# 10_RSSI1.net
KiCad netlist of a schematic drawn in Altium Designer
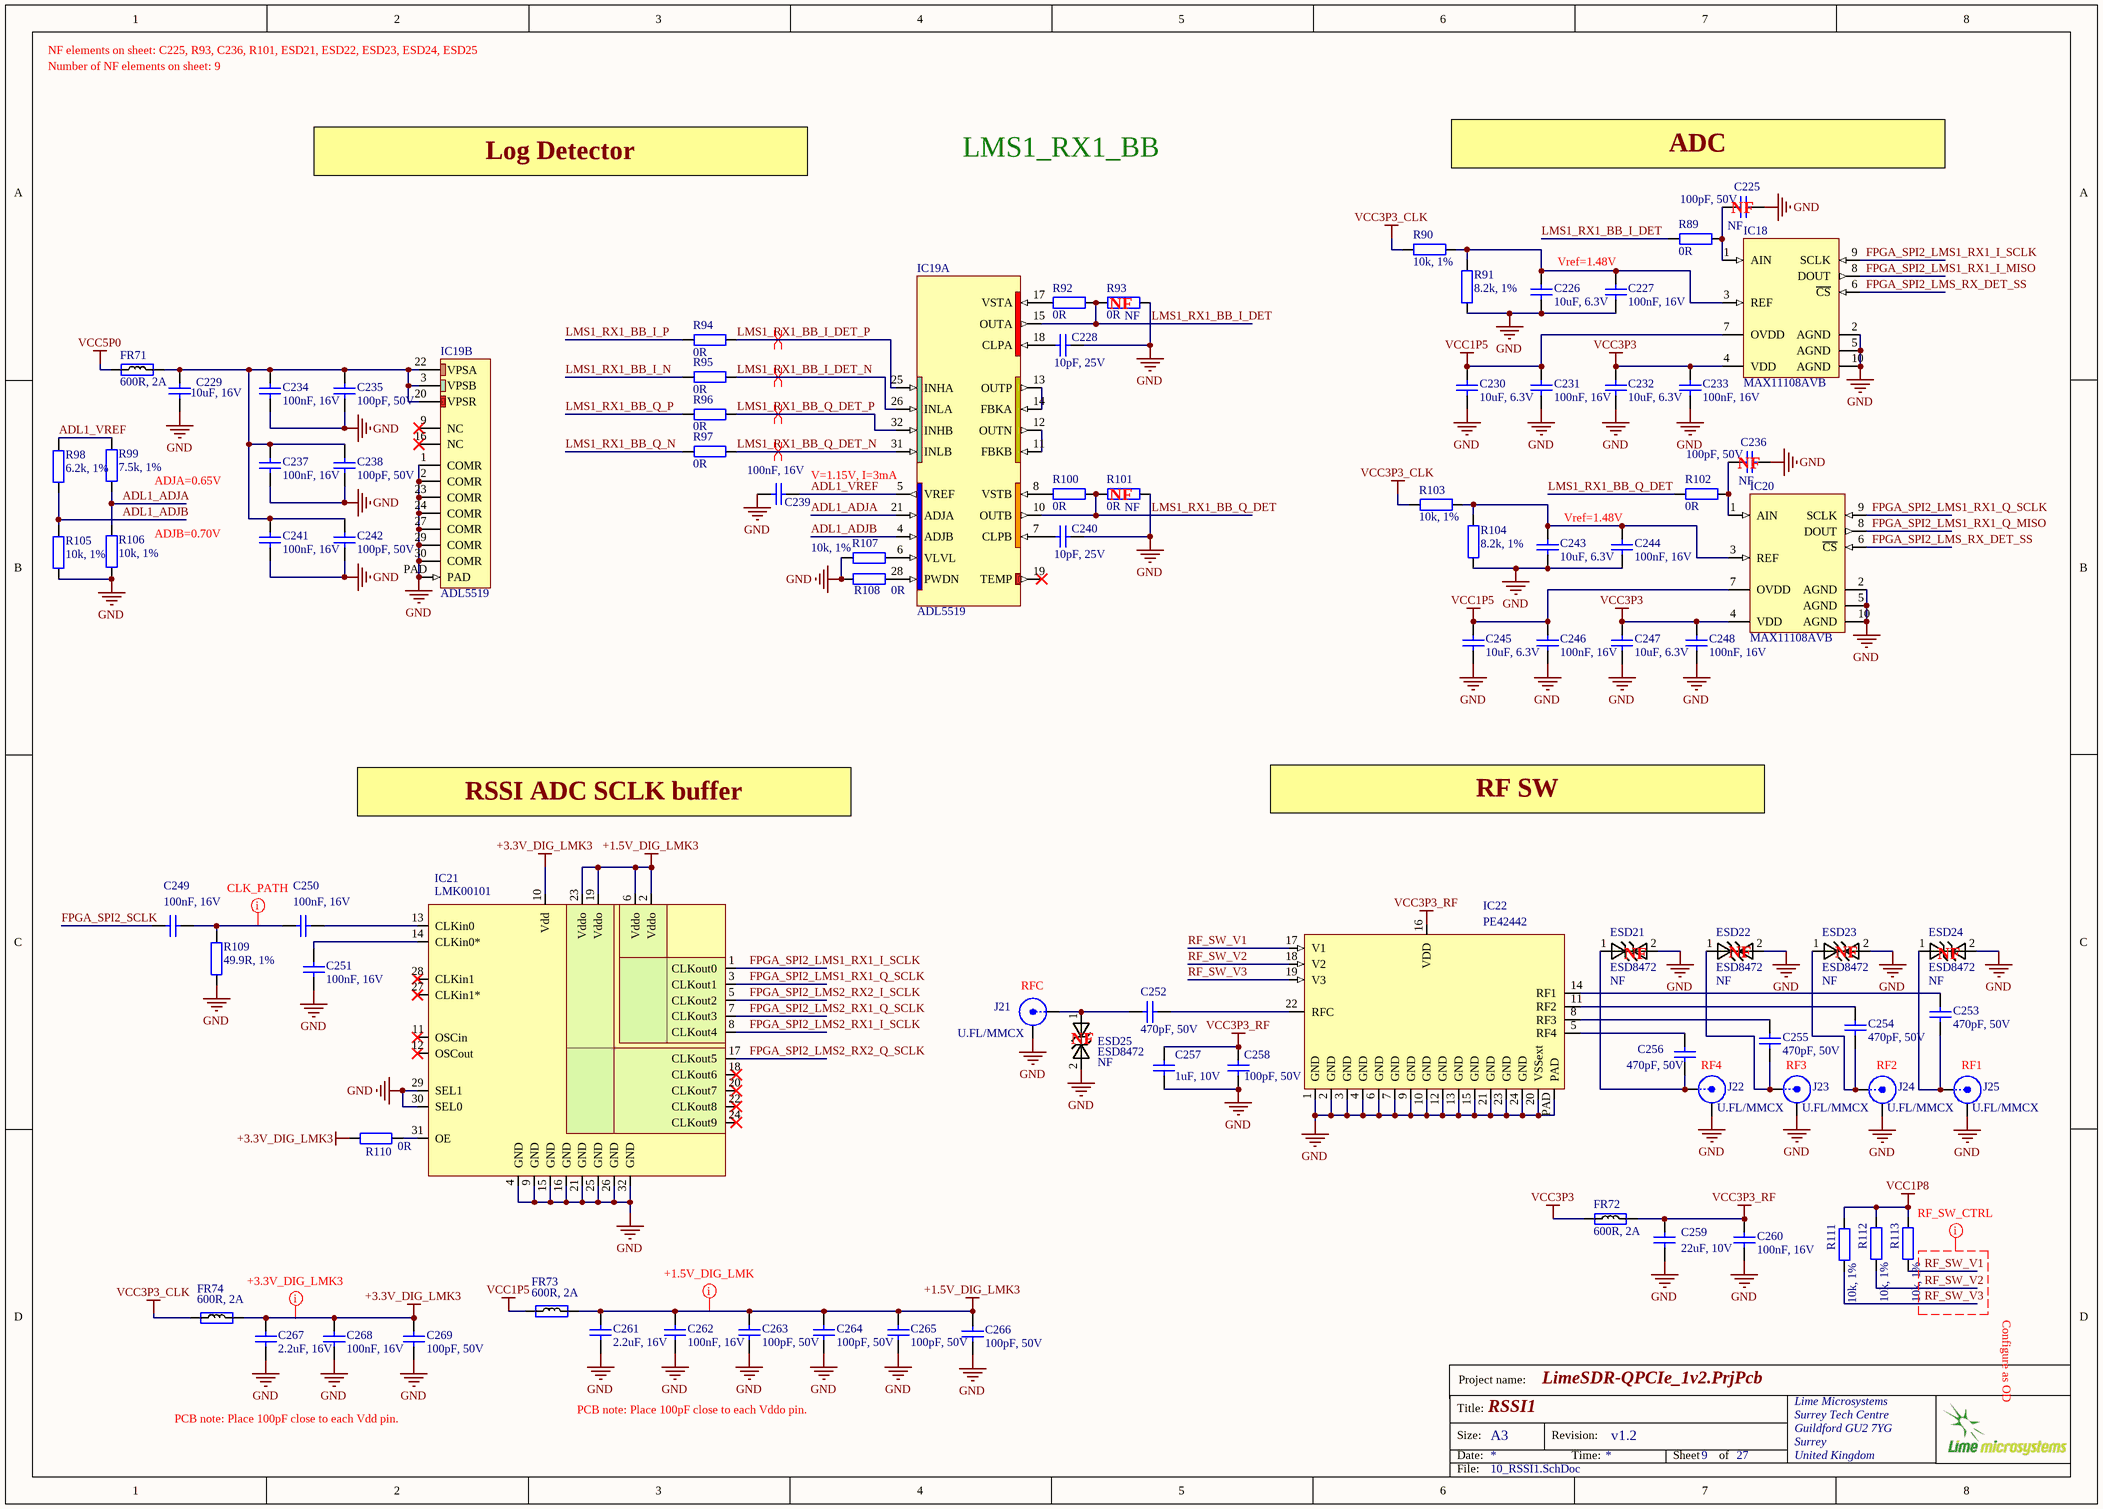
[diagram p0: 10_RSSI1.SchDoc]

(export (version "E")
  (design (tool "Eeschema 10.0.6"))
  (components
    (comp (ref "C225")
      (value "100pF, 50V")
      (footprint "CAP0402")
      (fields
        (field (name "ASSEMBLY INFO") "NF")
        (field (name "MANUFACTURER") "Yageo")
        (field (name "TOLERANCE") "±5%")
      )
      (libsource (lib "LimeMicroAltiumLib_schLib") (part "Cap_0402"))
    )
    (comp (ref "C226")
      (value "10uF, 6.3V")
      (footprint "CAP0603")
      (fields (field (name "TOLERANCE") "±20%") (field (name "MANUFACTURER") "Yageo"))
      (libsource (lib "LimeFPGAboard_schLib") (part "Cap_0603"))
    )
    (comp (ref "C227")
      (value "100nF, 16V")
      (footprint "CAP0402")
      (fields
        (field (name "MANUFACTURER") "Murata Electronics")
        (field (name "TOLERANCE") "10 %")
        (field (name "MANUFACTURER PART NUMBER") "GRM155R71C104KA88D")
      )
      (libsource (lib "LimeMicroAltiumLib_schLib") (part "Cap_0402"))
    )
    (comp (ref "C228")
      (value "10pF, 25V")
      (footprint "CAP0402")
      (fields (field (name "MANUFACTURER") "AVX"))
      (libsource (lib "LimeMicroAltiumLib_schLib") (part "Cap_0402"))
    )
    (comp (ref "C229")
      (value "10uF, 16V")
      (footprint "CAP0603")
      (fields (field (name "MANUFACTURER") "Yageo") (field (name "TOLERANCE") "±20%"))
      (libsource (lib "LimeMicroAltiumLib_schLib") (part "Cap_0603"))
    )
    (comp (ref "C230")
      (value "10uF, 6.3V")
      (footprint "CAP0603")
      (fields (field (name "TOLERANCE") "±20%") (field (name "MANUFACTURER") "Yageo"))
      (libsource (lib "LimeFPGAboard_schLib") (part "Cap_0603"))
    )
    (comp (ref "C231")
      (value "100nF, 16V")
      (footprint "CAP0402")
      (fields
        (field (name "MANUFACTURER") "Murata Electronics")
        (field (name "TOLERANCE") "10 %")
        (field (name "MANUFACTURER PART NUMBER") "GRM155R71C104KA88D")
      )
      (libsource (lib "LimeMicroAltiumLib_schLib") (part "Cap_0402"))
    )
    (comp (ref "C232")
      (value "10uF, 6.3V")
      (footprint "CAP0603")
      (fields (field (name "TOLERANCE") "±20%") (field (name "MANUFACTURER") "Yageo"))
      (libsource (lib "LimeFPGAboard_schLib") (part "Cap_0603"))
    )
    (comp (ref "C233")
      (value "100nF, 16V")
      (footprint "CAP0402")
      (fields
        (field (name "MANUFACTURER") "Murata Electronics")
        (field (name "TOLERANCE") "10 %")
        (field (name "MANUFACTURER PART NUMBER") "GRM155R71C104KA88D")
      )
      (libsource (lib "LimeMicroAltiumLib_schLib") (part "Cap_0402"))
    )
    (comp (ref "C234")
      (value "100nF, 16V")
      (footprint "CAP0402")
      (fields
        (field (name "MANUFACTURER") "Murata Electronics")
        (field (name "TOLERANCE") "10 %")
        (field (name "MANUFACTURER PART NUMBER") "GRM155R71C104KA88D")
      )
      (libsource (lib "LimeMicroAltiumLib_schLib") (part "Cap_0402"))
    )
    (comp (ref "C235")
      (value "100pF, 50V")
      (footprint "CAP0402")
      (fields (field (name "MANUFACTURER") "Yageo") (field (name "TOLERANCE") "±5%"))
      (libsource (lib "LimeMicroAltiumLib_schLib") (part "Cap_0402"))
    )
    (comp (ref "C236")
      (value "100pF, 50V")
      (footprint "CAP0402")
      (fields
        (field (name "ASSEMBLY INFO") "NF")
        (field (name "MANUFACTURER") "Yageo")
        (field (name "TOLERANCE") "±5%")
      )
      (libsource (lib "LimeMicroAltiumLib_schLib") (part "Cap_0402"))
    )
    (comp (ref "C237")
      (value "100nF, 16V")
      (footprint "CAP0402")
      (fields
        (field (name "MANUFACTURER") "Murata Electronics")
        (field (name "TOLERANCE") "10 %")
        (field (name "MANUFACTURER PART NUMBER") "GRM155R71C104KA88D")
      )
      (libsource (lib "LimeMicroAltiumLib_schLib") (part "Cap_0402"))
    )
    (comp (ref "C238")
      (value "100pF, 50V")
      (footprint "CAP0402")
      (fields (field (name "MANUFACTURER") "Yageo") (field (name "TOLERANCE") "±5%"))
      (libsource (lib "LimeMicroAltiumLib_schLib") (part "Cap_0402"))
    )
    (comp (ref "C239")
      (value "100nF, 16V")
      (footprint "CAP0402")
      (fields
        (field (name "MANUFACTURER") "Murata Electronics")
        (field (name "TOLERANCE") "10 %")
        (field (name "MANUFACTURER PART NUMBER") "GRM155R71C104KA88D")
      )
      (libsource (lib "LimeMicroAltiumLib_schLib") (part "Cap_0402"))
    )
    (comp (ref "C240")
      (value "10pF, 25V")
      (footprint "CAP0402")
      (fields (field (name "MANUFACTURER") "AVX"))
      (libsource (lib "LimeMicroAltiumLib_schLib") (part "Cap_0402"))
    )
    (comp (ref "C241")
      (value "100nF, 16V")
      (footprint "CAP0402")
      (fields
        (field (name "MANUFACTURER") "Murata Electronics")
        (field (name "TOLERANCE") "10 %")
        (field (name "MANUFACTURER PART NUMBER") "GRM155R71C104KA88D")
      )
      (libsource (lib "LimeMicroAltiumLib_schLib") (part "Cap_0402"))
    )
    (comp (ref "C242")
      (value "100pF, 50V")
      (footprint "CAP0402")
      (fields (field (name "MANUFACTURER") "Yageo") (field (name "TOLERANCE") "±5%"))
      (libsource (lib "LimeMicroAltiumLib_schLib") (part "Cap_0402"))
    )
    (comp (ref "C243")
      (value "10uF, 6.3V")
      (footprint "CAP0603")
      (fields (field (name "TOLERANCE") "±20%") (field (name "MANUFACTURER") "Yageo"))
      (libsource (lib "LimeFPGAboard_schLib") (part "Cap_0603"))
    )
    (comp (ref "C244")
      (value "100nF, 16V")
      (footprint "CAP0402")
      (fields
        (field (name "MANUFACTURER") "Murata Electronics")
        (field (name "TOLERANCE") "10 %")
        (field (name "MANUFACTURER PART NUMBER") "GRM155R71C104KA88D")
      )
      (libsource (lib "LimeMicroAltiumLib_schLib") (part "Cap_0402"))
    )
    (comp (ref "C245")
      (value "10uF, 6.3V")
      (footprint "CAP0603")
      (fields (field (name "TOLERANCE") "±20%") (field (name "MANUFACTURER") "Yageo"))
      (libsource (lib "LimeFPGAboard_schLib") (part "Cap_0603"))
    )
    (comp (ref "C246")
      (value "100nF, 16V")
      (footprint "CAP0402")
      (fields
        (field (name "MANUFACTURER") "Murata Electronics")
        (field (name "TOLERANCE") "10 %")
        (field (name "MANUFACTURER PART NUMBER") "GRM155R71C104KA88D")
      )
      (libsource (lib "LimeMicroAltiumLib_schLib") (part "Cap_0402"))
    )
    (comp (ref "C247")
      (value "10uF, 6.3V")
      (footprint "CAP0603")
      (fields (field (name "TOLERANCE") "±20%") (field (name "MANUFACTURER") "Yageo"))
      (libsource (lib "LimeFPGAboard_schLib") (part "Cap_0603"))
    )
    (comp (ref "C248")
      (value "100nF, 16V")
      (footprint "CAP0402")
      (fields
        (field (name "MANUFACTURER") "Murata Electronics")
        (field (name "TOLERANCE") "10 %")
        (field (name "MANUFACTURER PART NUMBER") "GRM155R71C104KA88D")
      )
      (libsource (lib "LimeMicroAltiumLib_schLib") (part "Cap_0402"))
    )
    (comp (ref "C249")
      (value "100nF, 16V")
      (footprint "CAP0402")
      (fields
        (field (name "MANUFACTURER") "Murata Electronics")
        (field (name "TOLERANCE") "10 %")
        (field (name "MANUFACTURER PART NUMBER") "GRM155R71C104KA88D")
      )
      (libsource (lib "LimeMicroAltiumLib_schLib") (part "Cap_0402"))
    )
    (comp (ref "C250")
      (value "100nF, 16V")
      (footprint "CAP0402")
      (fields
        (field (name "MANUFACTURER") "Murata Electronics")
        (field (name "TOLERANCE") "10 %")
        (field (name "MANUFACTURER PART NUMBER") "GRM155R71C104KA88D")
      )
      (libsource (lib "LimeMicroAltiumLib_schLib") (part "Cap_0402"))
    )
    (comp (ref "C251")
      (value "100nF, 16V")
      (footprint "CAP0402")
      (fields
        (field (name "MANUFACTURER") "Murata Electronics")
        (field (name "TOLERANCE") "10 %")
        (field (name "MANUFACTURER PART NUMBER") "GRM155R71C104KA88D")
      )
      (libsource (lib "LimeMicroAltiumLib_schLib") (part "Cap_0402"))
    )
    (comp (ref "C252")
      (value "470pF, 50V")
      (footprint "CAP0402")
      (fields
        (field (name "MANUFACTURER PART NUMBER") "C1005C0G1H471J050BA")
        (field (name "TOLERANCE") "±5%")
        (field (name "MANUFACTURER") "TDK Corporation")
      )
      (libsource (lib "LimeMicroAltiumLib_schLib") (part "Cap_0402"))
    )
    (comp (ref "C253")
      (value "470pF, 50V")
      (footprint "CAP0402")
      (fields
        (field (name "MANUFACTURER PART NUMBER") "C1005C0G1H471J050BA")
        (field (name "TOLERANCE") "±5%")
        (field (name "MANUFACTURER") "TDK Corporation")
      )
      (libsource (lib "LimeMicroAltiumLib_schLib") (part "Cap_0402"))
    )
    (comp (ref "C254")
      (value "470pF, 50V")
      (footprint "CAP0402")
      (fields
        (field (name "MANUFACTURER PART NUMBER") "C1005C0G1H471J050BA")
        (field (name "TOLERANCE") "±5%")
        (field (name "MANUFACTURER") "TDK Corporation")
      )
      (libsource (lib "LimeMicroAltiumLib_schLib") (part "Cap_0402"))
    )
    (comp (ref "C255")
      (value "470pF, 50V")
      (footprint "CAP0402")
      (fields
        (field (name "MANUFACTURER PART NUMBER") "C1005C0G1H471J050BA")
        (field (name "TOLERANCE") "±5%")
        (field (name "MANUFACTURER") "TDK Corporation")
      )
      (libsource (lib "LimeMicroAltiumLib_schLib") (part "Cap_0402"))
    )
    (comp (ref "C256")
      (value "470pF, 50V")
      (footprint "CAP0402")
      (fields
        (field (name "MANUFACTURER PART NUMBER") "C1005C0G1H471J050BA")
        (field (name "TOLERANCE") "±5%")
        (field (name "MANUFACTURER") "TDK Corporation")
      )
      (libsource (lib "LimeMicroAltiumLib_schLib") (part "Cap_0402"))
    )
    (comp (ref "C257")
      (value "1uF, 10V")
      (footprint "CAP0402")
      (fields (field (name "MANUFACTURER") "TDK"))
      (libsource (lib "LimeFPGAboard_schLib") (part "Cap_0603"))
    )
    (comp (ref "C258")
      (value "100pF, 50V")
      (footprint "CAP0402")
      (fields (field (name "MANUFACTURER") "Yageo") (field (name "TOLERANCE") "±5%"))
      (libsource (lib "LimeMicroAltiumLib_schLib") (part "Cap_0402"))
    )
    (comp (ref "C259")
      (value "22uF, 10V")
      (footprint "CAP0603")
      (fields (field (name "TOLERANCE") "20 %") (field (name "MANUFACTURER") "TDK Corporation"))
      (libsource (lib "LimeFPGAboard_schLib") (part "Cap_0603"))
    )
    (comp (ref "C260")
      (value "100nF, 16V")
      (footprint "CAP0402")
      (fields
        (field (name "MANUFACTURER") "Murata Electronics")
        (field (name "TOLERANCE") "10 %")
        (field (name "MANUFACTURER PART NUMBER") "GRM155R71C104KA88D")
      )
      (libsource (lib "LimeMicroAltiumLib_schLib") (part "Cap_0402"))
    )
    (comp (ref "C261")
      (value "2.2uF, 16V")
      (footprint "CAP0402")
      (description "CAP CER 2.2UF 16V 10% X5R 0402")
      (fields (field (name "MANUFACTURER") "TDK Corporation") (field (name "TOLERANCE") "±20%"))
      (libsource (lib "LimeMicroAltiumLib_schLib") (part "Cap_0402"))
    )
    (comp (ref "C262")
      (value "100nF, 16V")
      (footprint "CAP0402")
      (fields
        (field (name "MANUFACTURER") "Murata Electronics")
        (field (name "TOLERANCE") "10 %")
        (field (name "MANUFACTURER PART NUMBER") "GRM155R71C104KA88D")
      )
      (libsource (lib "LimeMicroAltiumLib_schLib") (part "Cap_0402"))
    )
    (comp (ref "C263")
      (value "100pF, 50V")
      (footprint "CAP0402")
      (fields (field (name "MANUFACTURER") "Yageo") (field (name "TOLERANCE") "±5%"))
      (libsource (lib "LimeMicroAltiumLib_schLib") (part "Cap_0402"))
    )
    (comp (ref "C264")
      (value "100pF, 50V")
      (footprint "CAP0402")
      (fields (field (name "MANUFACTURER") "Yageo") (field (name "TOLERANCE") "±5%"))
      (libsource (lib "LimeMicroAltiumLib_schLib") (part "Cap_0402"))
    )
    (comp (ref "C265")
      (value "100pF, 50V")
      (footprint "CAP0402")
      (fields (field (name "MANUFACTURER") "Yageo") (field (name "TOLERANCE") "±5%"))
      (libsource (lib "LimeMicroAltiumLib_schLib") (part "Cap_0402"))
    )
    (comp (ref "C266")
      (value "100pF, 50V")
      (footprint "CAP0402")
      (fields (field (name "MANUFACTURER") "Yageo") (field (name "TOLERANCE") "±5%"))
      (libsource (lib "LimeMicroAltiumLib_schLib") (part "Cap_0402"))
    )
    (comp (ref "C267")
      (value "2.2uF, 16V")
      (footprint "CAP0402")
      (description "CAP CER 2.2UF 16V 10% X5R 0402")
      (fields (field (name "MANUFACTURER") "TDK Corporation") (field (name "TOLERANCE") "±20%"))
      (libsource (lib "LimeMicroAltiumLib_schLib") (part "Cap_0402"))
    )
    (comp (ref "C268")
      (value "100nF, 16V")
      (footprint "CAP0402")
      (fields
        (field (name "MANUFACTURER") "Murata Electronics")
        (field (name "TOLERANCE") "10 %")
        (field (name "MANUFACTURER PART NUMBER") "GRM155R71C104KA88D")
      )
      (libsource (lib "LimeMicroAltiumLib_schLib") (part "Cap_0402"))
    )
    (comp (ref "C269")
      (value "100pF, 50V")
      (footprint "CAP0402")
      (fields (field (name "MANUFACTURER") "Yageo") (field (name "TOLERANCE") "±5%"))
      (libsource (lib "LimeMicroAltiumLib_schLib") (part "Cap_0402"))
    )
    (comp (ref "ESD21")
      (value "ESD8472")
      (footprint "ESD8472_X3DFN2")
      (fields
        (field (name "MANUFACTURER") "ON Semiconductor")
        (field (name "MANUFACTURER PART NUMBER") "ESD8472MUT5G")
        (field (name "ASSEMBLY INFO") "NF")
      )
      (libsource (lib "LimeMicroAltiumLib_schLib") (part "ESD8472"))
    )
    (comp (ref "ESD22")
      (value "ESD8472")
      (footprint "ESD8472_X3DFN2")
      (fields
        (field (name "MANUFACTURER") "ON Semiconductor")
        (field (name "MANUFACTURER PART NUMBER") "ESD8472MUT5G")
        (field (name "ASSEMBLY INFO") "NF")
      )
      (libsource (lib "LimeMicroAltiumLib_schLib") (part "ESD8472"))
    )
    (comp (ref "ESD23")
      (value "ESD8472")
      (footprint "ESD8472_X3DFN2")
      (fields
        (field (name "MANUFACTURER") "ON Semiconductor")
        (field (name "MANUFACTURER PART NUMBER") "ESD8472MUT5G")
        (field (name "ASSEMBLY INFO") "NF")
      )
      (libsource (lib "LimeMicroAltiumLib_schLib") (part "ESD8472"))
    )
    (comp (ref "ESD24")
      (value "ESD8472")
      (footprint "ESD8472_X3DFN2")
      (fields
        (field (name "MANUFACTURER") "ON Semiconductor")
        (field (name "MANUFACTURER PART NUMBER") "ESD8472MUT5G")
        (field (name "ASSEMBLY INFO") "NF")
      )
      (libsource (lib "LimeMicroAltiumLib_schLib") (part "ESD8472"))
    )
    (comp (ref "ESD25")
      (value "ESD8472")
      (footprint "ESD8472_X3DFN2")
      (fields
        (field (name "MANUFACTURER") "ON Semiconductor")
        (field (name "MANUFACTURER PART NUMBER") "ESD8472MUT5G")
        (field (name "ASSEMBLY INFO") "NF")
      )
      (libsource (lib "LimeMicroAltiumLib_schLib") (part "ESD8472"))
    )
    (comp (ref "FR71")
      (value "600R, 2A")
      (footprint "RES0805")
      (fields (field (name "MANUFACTURER") "TDK"))
      (libsource (lib "LimeMicroAltiumLib_schLib") (part "Ferrite"))
    )
    (comp (ref "FR72")
      (value "600R, 2A")
      (footprint "RES0805")
      (fields (field (name "MANUFACTURER") "TDK"))
      (libsource (lib "LimeFPGAboard_schLib") (part "Ferrite"))
    )
    (comp (ref "FR73")
      (value "600R, 2A")
      (footprint "RES0805")
      (fields (field (name "MANUFACTURER") "TDK"))
      (libsource (lib "LimeMicroAltiumLib_schLib") (part "Ferrite"))
    )
    (comp (ref "FR74")
      (value "600R, 2A")
      (footprint "RES0805")
      (fields (field (name "MANUFACTURER") "TDK"))
      (libsource (lib "LimeMicroAltiumLib_schLib") (part "Ferrite"))
    )
    (comp (ref "IC18")
      (value "MAX11108AVB")
      (footprint "MAX11108AVB+T")
      (fields (field (name "MANUFACTURER") "Maxim Integrated"))
      (libsource (lib "LimeMicroAltiumLib_schLib") (part "MAX11108AVB+T"))
    )
    (comp (ref "IC19")
      (value "ADL5519")
      (footprint "ADL5519_32LFCSP")
      (fields (field (name "MANUFACTURER") "Analog Devices Inc."))
      (libsource (lib "LimeMicroAltiumLib_schLib") (part "ADL5519"))
    )
    (comp (ref "IC20")
      (value "MAX11108AVB")
      (footprint "MAX11108AVB+T")
      (fields (field (name "MANUFACTURER") "Maxim Integrated"))
      (libsource (lib "LimeMicroAltiumLib_schLib") (part "MAX11108AVB+T"))
    )
    (comp (ref "IC21")
      (value "LMK00101")
      (footprint "LMK00101_WQFN32")
      (fields (field (name "MANUFACTURER") "Texas Instruments"))
      (libsource (lib "LimeMicroAltiumLib_schLib") (part "LMK00101"))
    )
    (comp (ref "IC22")
      (value "PE42442")
      (footprint "PE42442_24QFN")
      (description "UltraCMOS SPDT RF Switch  100 – 6000 MHz")
      (fields (field (name "MANUFACTURER") "Peregrine Semiconductor"))
      (libsource (lib "LimeMicroAltiumLib_schLib") (part "PE42442"))
    )
    (comp (ref "J21")
      (value "U.FL/MMCX")
      (footprint "MMCX_UFL_conn_U")
      (description "CONN UMC RCPT STR 50 OHM SMD")
      (fields (field (name "MANUFACTURER") "Molex, LLC"))
      (libsource (lib "LimeMicroAltiumLib_schLib") (part "RF_IF_connector"))
    )
    (comp (ref "J22")
      (value "U.FL/MMCX")
      (footprint "MMCX_UFL_conn_U")
      (description "CONN UMC RCPT STR 50 OHM SMD")
      (fields (field (name "MANUFACTURER") "Molex, LLC"))
      (libsource (lib "LimeMicroAltiumLib_schLib") (part "RF_IF_connector"))
    )
    (comp (ref "J23")
      (value "U.FL/MMCX")
      (footprint "MMCX_UFL_conn_U")
      (description "CONN UMC RCPT STR 50 OHM SMD")
      (fields (field (name "MANUFACTURER") "Molex, LLC"))
      (libsource (lib "LimeMicroAltiumLib_schLib") (part "RF_IF_connector"))
    )
    (comp (ref "J24")
      (value "U.FL/MMCX")
      (footprint "MMCX_UFL_conn_U")
      (description "CONN UMC RCPT STR 50 OHM SMD")
      (fields (field (name "MANUFACTURER") "Molex, LLC"))
      (libsource (lib "LimeMicroAltiumLib_schLib") (part "RF_IF_connector"))
    )
    (comp (ref "J25")
      (value "U.FL/MMCX")
      (footprint "MMCX_UFL_conn_U")
      (description "CONN UMC RCPT STR 50 OHM SMD")
      (fields (field (name "MANUFACTURER") "Molex, LLC"))
      (libsource (lib "LimeMicroAltiumLib_schLib") (part "RF_IF_connector"))
    )
    (comp (ref "R89")
      (value "0R")
      (footprint "RES0402")
      (fields (field (name "MANUFACTURER") "Yageo") (field (name "TOLERANCE") "Jumper"))
      (libsource (lib "LimeMicroAltiumLib_schLib") (part "Res_0402"))
    )
    (comp (ref "R90")
      (value "10k, 1%")
      (footprint "RES0402")
      (fields (field (name "MANUFACTURER") "Yageo") (field (name "TOLERANCE") "±1%"))
      (libsource (lib "LimeMicroAltiumLib_schLib") (part "Res_0402"))
    )
    (comp (ref "R91")
      (value "8.2k, 1%")
      (footprint "RES0402")
      (fields (field (name "MANUFACTURER") "Yageo") (field (name "TOLERANCE") "±1%"))
      (libsource (lib "LimeMicroAltiumLib_schLib") (part "Res_0402"))
    )
    (comp (ref "R92")
      (value "0R")
      (footprint "RES0402")
      (fields (field (name "MANUFACTURER") "Yageo") (field (name "TOLERANCE") "Jumper"))
      (libsource (lib "LimeMicroAltiumLib_schLib") (part "Res_0402"))
    )
    (comp (ref "R93")
      (value "0R")
      (footprint "RES0402")
      (fields
        (field (name "ASSEMBLY INFO") "NF")
        (field (name "MANUFACTURER") "Yageo")
        (field (name "TOLERANCE") "Jumper")
      )
      (libsource (lib "LimeMicroAltiumLib_schLib") (part "Res_0402"))
    )
    (comp (ref "R94")
      (value "0R")
      (footprint "RES0402")
      (fields (field (name "MANUFACTURER") "Yageo") (field (name "TOLERANCE") "Jumper"))
      (libsource (lib "LimeMicroAltiumLib_schLib") (part "Res_0402"))
    )
    (comp (ref "R95")
      (value "0R")
      (footprint "RES0402")
      (fields (field (name "MANUFACTURER") "Yageo") (field (name "TOLERANCE") "Jumper"))
      (libsource (lib "LimeMicroAltiumLib_schLib") (part "Res_0402"))
    )
    (comp (ref "R96")
      (value "0R")
      (footprint "RES0402")
      (fields (field (name "MANUFACTURER") "Yageo") (field (name "TOLERANCE") "Jumper"))
      (libsource (lib "LimeMicroAltiumLib_schLib") (part "Res_0402"))
    )
    (comp (ref "R97")
      (value "0R")
      (footprint "RES0402")
      (fields (field (name "MANUFACTURER") "Yageo") (field (name "TOLERANCE") "Jumper"))
      (libsource (lib "LimeMicroAltiumLib_schLib") (part "Res_0402"))
    )
    (comp (ref "R98")
      (value "6.2k, 1%")
      (footprint "RES0402")
      (fields
        (field (name "MANUFACTURER") "Yageo")
        (field (name "MANUFACTURER PART NUMBER") "RC0402FR-076K2L")
        (field (name "TOLERANCE") "±1%")
      )
      (libsource (lib "LimeMicroAltiumLib_schLib") (part "Res_0402"))
    )
    (comp (ref "R99")
      (value "7.5k, 1%")
      (footprint "RES0402")
      (fields
        (field (name "TOLERANCE") "±1%")
        (field (name "MANUFACTURER PART NUMBER") "RC0402FR-077K5L")
        (field (name "MANUFACTURER") "Yageo")
      )
      (libsource (lib "LimeMicroAltiumLib_schLib") (part "Res_0402"))
    )
    (comp (ref "R100")
      (value "0R")
      (footprint "RES0402")
      (fields (field (name "MANUFACTURER") "Yageo") (field (name "TOLERANCE") "Jumper"))
      (libsource (lib "LimeMicroAltiumLib_schLib") (part "Res_0402"))
    )
    (comp (ref "R101")
      (value "0R")
      (footprint "RES0402")
      (fields
        (field (name "ASSEMBLY INFO") "NF")
        (field (name "MANUFACTURER") "Yageo")
        (field (name "TOLERANCE") "Jumper")
      )
      (libsource (lib "LimeMicroAltiumLib_schLib") (part "Res_0402"))
    )
    (comp (ref "R102")
      (value "0R")
      (footprint "RES0402")
      (fields (field (name "MANUFACTURER") "Yageo") (field (name "TOLERANCE") "Jumper"))
      (libsource (lib "LimeMicroAltiumLib_schLib") (part "Res_0402"))
    )
    (comp (ref "R103")
      (value "10k, 1%")
      (footprint "RES0402")
      (fields (field (name "MANUFACTURER") "Yageo") (field (name "TOLERANCE") "±1%"))
      (libsource (lib "LimeMicroAltiumLib_schLib") (part "Res_0402"))
    )
    (comp (ref "R104")
      (value "8.2k, 1%")
      (footprint "RES0402")
      (fields (field (name "MANUFACTURER") "Yageo") (field (name "TOLERANCE") "±1%"))
      (libsource (lib "LimeMicroAltiumLib_schLib") (part "Res_0402"))
    )
    (comp (ref "R105")
      (value "10k, 1%")
      (footprint "RES0402")
      (fields (field (name "MANUFACTURER") "Yageo") (field (name "TOLERANCE") "±1%"))
      (libsource (lib "LimeMicroAltiumLib_schLib") (part "Res_0402"))
    )
    (comp (ref "R106")
      (value "10k, 1%")
      (footprint "RES0402")
      (fields (field (name "MANUFACTURER") "Yageo") (field (name "TOLERANCE") "±1%"))
      (libsource (lib "LimeMicroAltiumLib_schLib") (part "Res_0402"))
    )
    (comp (ref "R107")
      (value "10k, 1%")
      (footprint "RES0402")
      (fields (field (name "MANUFACTURER") "Yageo") (field (name "TOLERANCE") "±1%"))
      (libsource (lib "LimeMicroAltiumLib_schLib") (part "Res_0402"))
    )
    (comp (ref "R108")
      (value "0R")
      (footprint "RES0402")
      (fields (field (name "MANUFACTURER") "Yageo") (field (name "TOLERANCE") "Jumper"))
      (libsource (lib "LimeMicroAltiumLib_schLib") (part "Res_0402"))
    )
    (comp (ref "R109")
      (value "49.9R, 1%")
      (footprint "RES0402")
      (fields
        (field (name "TOLERANCE") "±1%")
        (field (name "MANUFACTURER") "Samsung Electro-Mechanics America, Inc.")
      )
      (libsource (lib "LimeMicroAltiumLib_schLib") (part "Res_0402"))
    )
    (comp (ref "R110")
      (value "0R")
      (footprint "RES0402")
      (fields (field (name "MANUFACTURER") "Yageo") (field (name "TOLERANCE") "Jumper"))
      (libsource (lib "LimeMicroAltiumLib_schLib") (part "Res_0402"))
    )
    (comp (ref "R111")
      (value "10k, 1%")
      (footprint "RES0402")
      (fields (field (name "MANUFACTURER") "Yageo") (field (name "TOLERANCE") "±1%"))
      (libsource (lib "LimeMicroAltiumLib_schLib") (part "Res_0402"))
    )
    (comp (ref "R112")
      (value "10k, 1%")
      (footprint "RES0402")
      (fields (field (name "MANUFACTURER") "Yageo") (field (name "TOLERANCE") "±1%"))
      (libsource (lib "LimeMicroAltiumLib_schLib") (part "Res_0402"))
    )
    (comp (ref "R113")
      (value "10k, 1%")
      (footprint "RES0402")
      (fields (field (name "MANUFACTURER") "Yageo") (field (name "TOLERANCE") "±1%"))
      (libsource (lib "LimeMicroAltiumLib_schLib") (part "Res_0402"))
    )
  )
  (nets
    (net (code "1") (name "+1.5V_DIG_LMK3") (class "Default")
      (node (ref "C261") (pin "2") (pinfunction "2_2") (pintype "passive"))
      (node (ref "C262") (pin "2") (pinfunction "2_2") (pintype "passive"))
      (node (ref "C263") (pin "2") (pinfunction "2_2") (pintype "passive"))
      (node (ref "C264") (pin "2") (pinfunction "2_2") (pintype "passive"))
      (node (ref "C265") (pin "2") (pinfunction "2_2") (pintype "passive"))
      (node (ref "C266") (pin "2") (pinfunction "2_2") (pintype "passive"))
      (node (ref "FR73") (pin "2") (pinfunction "2_2") (pintype "passive"))
      (node (ref "IC21") (pin "19") (pinfunction "Vddo_19") (pintype "power_in"))
      (node (ref "IC21") (pin "2") (pinfunction "Vddo_2") (pintype "power_in"))
      (node (ref "IC21") (pin "23") (pinfunction "Vddo_23") (pintype "power_in"))
      (node (ref "IC21") (pin "6") (pinfunction "Vddo_6") (pintype "power_in"))
    )
    (net (code "2") (name "+3.3V_DIG_LMK3") (class "Default")
      (node (ref "C267") (pin "2") (pinfunction "2_2") (pintype "passive"))
      (node (ref "C268") (pin "2") (pinfunction "2_2") (pintype "passive"))
      (node (ref "C269") (pin "2") (pinfunction "2_2") (pintype "passive"))
      (node (ref "FR74") (pin "2") (pinfunction "2_2") (pintype "passive"))
      (node (ref "IC21") (pin "10") (pinfunction "Vdd_10") (pintype "power_in"))
      (node (ref "R110") (pin "1") (pinfunction "1_1") (pintype "passive"))
    )
    (net (code "3") (name "/ADL1_ADJA") (class "Default")
      (node (ref "IC19") (pin "21") (pinfunction "ADJA_21") (pintype "input"))
      (node (ref "R106") (pin "1") (pinfunction "1_1") (pintype "passive"))
      (node (ref "R99") (pin "1") (pinfunction "1_1") (pintype "passive"))
    )
    (net (code "4") (name "/ADL1_ADJB") (class "Default")
      (node (ref "IC19") (pin "4") (pinfunction "ADJB_4") (pintype "input"))
      (node (ref "R105") (pin "2") (pinfunction "2_2") (pintype "passive"))
      (node (ref "R98") (pin "1") (pinfunction "1_1") (pintype "passive"))
    )
    (net (code "5") (name "/ADL1_VREF") (class "Default")
      (node (ref "C239") (pin "1") (pinfunction "1_1") (pintype "passive"))
      (node (ref "IC19") (pin "5") (pinfunction "VREF_5") (pintype "output"))
      (node (ref "R98") (pin "2") (pinfunction "2_2") (pintype "passive"))
      (node (ref "R99") (pin "2") (pinfunction "2_2") (pintype "passive"))
    )
    (net (code "6") (name "/FPGA_SPI2_LMS1_RX1_I_MISO") (class "Default")
      (node (ref "IC18") (pin "8") (pinfunction "DOUT_8") (pintype "output"))
    )
    (net (code "7") (name "/FPGA_SPI2_LMS1_RX1_I_SCLK") (class "Default")
      (node (ref "IC18") (pin "9") (pinfunction "SCLK_9") (pintype "input"))
      (node (ref "IC21") (pin "1") (pinfunction "CLKout0_1") (pintype "output"))
    )
    (net (code "8") (name "/FPGA_SPI2_LMS1_RX1_Q_MISO") (class "Default")
      (node (ref "IC20") (pin "8") (pinfunction "DOUT_8") (pintype "output"))
    )
    (net (code "9") (name "/FPGA_SPI2_LMS1_RX1_Q_SCLK") (class "Default")
      (node (ref "IC20") (pin "9") (pinfunction "SCLK_9") (pintype "input"))
      (node (ref "IC21") (pin "3") (pinfunction "CLKout1_3") (pintype "output"))
    )
    (net (code "10") (name "/FPGA_SPI2_LMS2_RX1_I_SCLK") (class "Default")
      (node (ref "IC21") (pin "8") (pinfunction "CLKout4_8") (pintype "output"))
    )
    (net (code "11") (name "/FPGA_SPI2_LMS2_RX1_Q_SCLK") (class "Default")
      (node (ref "IC21") (pin "7") (pinfunction "CLKout3_7") (pintype "output"))
    )
    (net (code "12") (name "/FPGA_SPI2_LMS2_RX2_I_SCLK") (class "Default")
      (node (ref "IC21") (pin "5") (pinfunction "CLKout2_5") (pintype "output"))
    )
    (net (code "13") (name "/FPGA_SPI2_LMS2_RX2_Q_SCLK") (class "Default")
      (node (ref "IC21") (pin "17") (pinfunction "CLKout5_17") (pintype "output"))
    )
    (net (code "14") (name "/FPGA_SPI2_LMS_RX_DET_SS") (class "Default")
      (node (ref "IC18") (pin "6") (pinfunction "~{CS}_6") (pintype "input"))
      (node (ref "IC20") (pin "6") (pinfunction "~{CS}_6") (pintype "input"))
    )
    (net (code "15") (name "/FPGA_SPI2_SCLK") (class "Default")
      (node (ref "C249") (pin "2") (pinfunction "2_2") (pintype "passive"))
    )
    (net (code "16") (name "/LMS1_RX1_BB_I_DET") (class "Default")
      (node (ref "IC19") (pin "15") (pinfunction "OUTA_15") (pintype "output"))
      (node (ref "R89") (pin "2") (pinfunction "2_2") (pintype "passive"))
      (node (ref "R92") (pin "1") (pinfunction "1_1") (pintype "passive"))
      (node (ref "R93") (pin "2") (pinfunction "2_2") (pintype "passive"))
    )
    (net (code "17") (name "/LMS1_RX1_BB_I_DET_N") (class "Default")
      (node (ref "IC19") (pin "26") (pinfunction "INLA_26") (pintype "input"))
      (node (ref "R95") (pin "1") (pinfunction "1_1") (pintype "passive"))
    )
    (net (code "18") (name "/LMS1_RX1_BB_I_DET_P") (class "Default")
      (node (ref "IC19") (pin "25") (pinfunction "INHA_25") (pintype "input"))
      (node (ref "R94") (pin "1") (pinfunction "1_1") (pintype "passive"))
    )
    (net (code "19") (name "/LMS1_RX1_BB_I_N") (class "Default")
      (node (ref "R95") (pin "2") (pinfunction "2_2") (pintype "passive"))
    )
    (net (code "20") (name "/LMS1_RX1_BB_I_P") (class "Default")
      (node (ref "R94") (pin "2") (pinfunction "2_2") (pintype "passive"))
    )
    (net (code "21") (name "/LMS1_RX1_BB_Q_DET") (class "Default")
      (node (ref "IC19") (pin "10") (pinfunction "OUTB_10") (pintype "output"))
      (node (ref "R100") (pin "1") (pinfunction "1_1") (pintype "passive"))
      (node (ref "R101") (pin "2") (pinfunction "2_2") (pintype "passive"))
      (node (ref "R102") (pin "2") (pinfunction "2_2") (pintype "passive"))
    )
    (net (code "22") (name "/LMS1_RX1_BB_Q_DET_N") (class "Default")
      (node (ref "IC19") (pin "31") (pinfunction "INLB_31") (pintype "input"))
      (node (ref "R97") (pin "1") (pinfunction "1_1") (pintype "passive"))
    )
    (net (code "23") (name "/LMS1_RX1_BB_Q_DET_P") (class "Default")
      (node (ref "IC19") (pin "32") (pinfunction "INHB_32") (pintype "input"))
      (node (ref "R96") (pin "1") (pinfunction "1_1") (pintype "passive"))
    )
    (net (code "24") (name "/LMS1_RX1_BB_Q_N") (class "Default")
      (node (ref "R97") (pin "2") (pinfunction "2_2") (pintype "passive"))
    )
    (net (code "25") (name "/LMS1_RX1_BB_Q_P") (class "Default")
      (node (ref "R96") (pin "2") (pinfunction "2_2") (pintype "passive"))
    )
    (net (code "26") (name "/RF_SW_V1") (class "Default")
      (node (ref "IC22") (pin "17") (pinfunction "V1_17") (pintype "input"))
      (node (ref "R113") (pin "2") (pinfunction "2_2") (pintype "passive"))
    )
    (net (code "27") (name "/RF_SW_V2") (class "Default")
      (node (ref "IC22") (pin "18") (pinfunction "V2_18") (pintype "input"))
      (node (ref "R112") (pin "2") (pinfunction "2_2") (pintype "passive"))
    )
    (net (code "28") (name "/RF_SW_V3") (class "Default")
      (node (ref "IC22") (pin "19") (pinfunction "V3_19") (pintype "input"))
      (node (ref "R111") (pin "2") (pinfunction "2_2") (pintype "passive"))
    )
    (net (code "29") (name "GND") (class "Default")
      (node (ref "C225") (pin "1") (pinfunction "1_1") (pintype "passive"))
      (node (ref "C226") (pin "1") (pinfunction "1_1") (pintype "passive"))
      (node (ref "C227") (pin "2") (pinfunction "2_2") (pintype "passive"))
      (node (ref "C228") (pin "2") (pinfunction "2_2") (pintype "passive"))
      (node (ref "C229") (pin "1") (pinfunction "1_1") (pintype "passive"))
      (node (ref "C230") (pin "1") (pinfunction "1_1") (pintype "passive"))
      (node (ref "C231") (pin "2") (pinfunction "2_2") (pintype "passive"))
      (node (ref "C232") (pin "1") (pinfunction "1_1") (pintype "passive"))
      (node (ref "C233") (pin "2") (pinfunction "2_2") (pintype "passive"))
      (node (ref "C234") (pin "1") (pinfunction "1_1") (pintype "passive"))
      (node (ref "C235") (pin "1") (pinfunction "1_1") (pintype "passive"))
      (node (ref "C236") (pin "1") (pinfunction "1_1") (pintype "passive"))
      (node (ref "C237") (pin "1") (pinfunction "1_1") (pintype "passive"))
      (node (ref "C238") (pin "1") (pinfunction "1_1") (pintype "passive"))
      (node (ref "C239") (pin "2") (pinfunction "2_2") (pintype "passive"))
      (node (ref "C240") (pin "2") (pinfunction "2_2") (pintype "passive"))
      (node (ref "C241") (pin "1") (pinfunction "1_1") (pintype "passive"))
      (node (ref "C242") (pin "1") (pinfunction "1_1") (pintype "passive"))
      (node (ref "C243") (pin "1") (pinfunction "1_1") (pintype "passive"))
      (node (ref "C244") (pin "2") (pinfunction "2_2") (pintype "passive"))
      (node (ref "C245") (pin "1") (pinfunction "1_1") (pintype "passive"))
      (node (ref "C246") (pin "2") (pinfunction "2_2") (pintype "passive"))
      (node (ref "C247") (pin "1") (pinfunction "1_1") (pintype "passive"))
      (node (ref "C248") (pin "2") (pinfunction "2_2") (pintype "passive"))
      (node (ref "C251") (pin "1") (pinfunction "1_1") (pintype "passive"))
      (node (ref "C257") (pin "1") (pinfunction "1_1") (pintype "passive"))
      (node (ref "C258") (pin "1") (pinfunction "1_1") (pintype "passive"))
      (node (ref "C259") (pin "1") (pinfunction "1_1") (pintype "passive"))
      (node (ref "C260") (pin "1") (pinfunction "1_1") (pintype "passive"))
      (node (ref "C261") (pin "1") (pinfunction "1_1") (pintype "passive"))
      (node (ref "C262") (pin "1") (pinfunction "1_1") (pintype "passive"))
      (node (ref "C263") (pin "1") (pinfunction "1_1") (pintype "passive"))
      (node (ref "C264") (pin "1") (pinfunction "1_1") (pintype "passive"))
      (node (ref "C265") (pin "1") (pinfunction "1_1") (pintype "passive"))
      (node (ref "C266") (pin "1") (pinfunction "1_1") (pintype "passive"))
      (node (ref "C267") (pin "1") (pinfunction "1_1") (pintype "passive"))
      (node (ref "C268") (pin "1") (pinfunction "1_1") (pintype "passive"))
      (node (ref "C269") (pin "1") (pinfunction "1_1") (pintype "passive"))
      (node (ref "ESD21") (pin "2") (pinfunction "2_2") (pintype "passive"))
      (node (ref "ESD22") (pin "2") (pinfunction "2_2") (pintype "passive"))
      (node (ref "ESD23") (pin "2") (pinfunction "2_2") (pintype "passive"))
      (node (ref "ESD24") (pin "2") (pinfunction "2_2") (pintype "passive"))
      (node (ref "ESD25") (pin "2") (pinfunction "2_2") (pintype "passive"))
      (node (ref "IC18") (pin "10") (pinfunction "AGND_10") (pintype "passive"))
      (node (ref "IC18") (pin "2") (pinfunction "AGND_2") (pintype "passive"))
      (node (ref "IC18") (pin "5") (pinfunction "AGND_5") (pintype "passive"))
      (node (ref "IC19") (pin "1") (pinfunction "COMR_1") (pintype "passive"))
      (node (ref "IC19") (pin "2") (pinfunction "COMR_2") (pintype "passive"))
      (node (ref "IC19") (pin "23") (pinfunction "COMR_23") (pintype "passive"))
      (node (ref "IC19") (pin "24") (pinfunction "COMR_24") (pintype "passive"))
      (node (ref "IC19") (pin "27") (pinfunction "COMR_27") (pintype "passive"))
      (node (ref "IC19") (pin "29") (pinfunction "COMR_29") (pintype "passive"))
      (node (ref "IC19") (pin "30") (pinfunction "COMR_30") (pintype "passive"))
      (node (ref "IC19") (pin "PAD") (pinfunction "PAD_PAD") (pintype "input"))
      (node (ref "IC20") (pin "10") (pinfunction "AGND_10") (pintype "passive"))
      (node (ref "IC20") (pin "2") (pinfunction "AGND_2") (pintype "passive"))
      (node (ref "IC20") (pin "5") (pinfunction "AGND_5") (pintype "passive"))
      (node (ref "IC21") (pin "15") (pinfunction "GND_15") (pintype "passive"))
      (node (ref "IC21") (pin "16") (pinfunction "GND_16") (pintype "passive"))
      (node (ref "IC21") (pin "21") (pinfunction "GND_21") (pintype "passive"))
      (node (ref "IC21") (pin "25") (pinfunction "GND_25") (pintype "passive"))
      (node (ref "IC21") (pin "26") (pinfunction "GND_26") (pintype "passive"))
      (node (ref "IC21") (pin "29") (pinfunction "SEL1_29") (pintype "input"))
      (node (ref "IC21") (pin "30") (pinfunction "SEL0_30") (pintype "input"))
      (node (ref "IC21") (pin "32") (pinfunction "GND_32") (pintype "passive"))
      (node (ref "IC21") (pin "4") (pinfunction "GND_4") (pintype "passive"))
      (node (ref "IC21") (pin "9") (pinfunction "GND_9") (pintype "passive"))
      (node (ref "IC22") (pin "1") (pinfunction "GND_1") (pintype "passive"))
      (node (ref "IC22") (pin "10") (pinfunction "GND_10") (pintype "passive"))
      (node (ref "IC22") (pin "12") (pinfunction "GND_12") (pintype "passive"))
      (node (ref "IC22") (pin "13") (pinfunction "GND_13") (pintype "passive"))
      (node (ref "IC22") (pin "15") (pinfunction "GND_15") (pintype "passive"))
      (node (ref "IC22") (pin "2") (pinfunction "GND_2") (pintype "passive"))
      (node (ref "IC22") (pin "20") (pinfunction "VSSext_20") (pintype "passive"))
      (node (ref "IC22") (pin "21") (pinfunction "GND_21") (pintype "passive"))
      (node (ref "IC22") (pin "23") (pinfunction "GND_23") (pintype "passive"))
      (node (ref "IC22") (pin "24") (pinfunction "GND_24") (pintype "passive"))
      (node (ref "IC22") (pin "3") (pinfunction "GND_3") (pintype "passive"))
      (node (ref "IC22") (pin "4") (pinfunction "GND_4") (pintype "passive"))
      (node (ref "IC22") (pin "6") (pinfunction "GND_6") (pintype "passive"))
      (node (ref "IC22") (pin "7") (pinfunction "GND_7") (pintype "passive"))
      (node (ref "IC22") (pin "9") (pinfunction "GND_9") (pintype "passive"))
      (node (ref "IC22") (pin "PAD") (pinfunction "PAD_PAD") (pintype "passive"))
      (node (ref "J21") (pin "2") (pinfunction "Y_2") (pintype "passive"))
      (node (ref "J22") (pin "2") (pinfunction "Y_2") (pintype "passive"))
      (node (ref "J23") (pin "2") (pinfunction "Y_2") (pintype "passive"))
      (node (ref "J24") (pin "2") (pinfunction "Y_2") (pintype "passive"))
      (node (ref "J25") (pin "2") (pinfunction "Y_2") (pintype "passive"))
      (node (ref "R101") (pin "1") (pinfunction "1_1") (pintype "passive"))
      (node (ref "R104") (pin "1") (pinfunction "1_1") (pintype "passive"))
      (node (ref "R105") (pin "1") (pinfunction "1_1") (pintype "passive"))
      (node (ref "R106") (pin "2") (pinfunction "2_2") (pintype "passive"))
      (node (ref "R107") (pin "2") (pinfunction "2_2") (pintype "passive"))
      (node (ref "R108") (pin "2") (pinfunction "2_2") (pintype "passive"))
      (node (ref "R109") (pin "1") (pinfunction "1_1") (pintype "passive"))
      (node (ref "R91") (pin "1") (pinfunction "1_1") (pintype "passive"))
      (node (ref "R93") (pin "1") (pinfunction "1_1") (pintype "passive"))
    )
    (net (code "30") (name "Net-(C249-Pad1)") (class "Default")
      (node (ref "C249") (pin "1") (pinfunction "1_1") (pintype "passive"))
      (node (ref "C250") (pin "2") (pinfunction "2_2") (pintype "passive"))
      (node (ref "R109") (pin "2") (pinfunction "2_2") (pintype "passive"))
    )
    (net (code "31") (name "Net-(IC18-AIN)") (class "Default")
      (node (ref "C225") (pin "2") (pinfunction "2_2") (pintype "passive"))
      (node (ref "IC18") (pin "1") (pinfunction "AIN_1") (pintype "input"))
      (node (ref "R89") (pin "1") (pinfunction "1_1") (pintype "passive"))
    )
    (net (code "32") (name "Net-(IC18-REF)") (class "Default")
      (node (ref "C226") (pin "2") (pinfunction "2_2") (pintype "passive"))
      (node (ref "C227") (pin "1") (pinfunction "1_1") (pintype "passive"))
      (node (ref "IC18") (pin "3") (pinfunction "REF_3") (pintype "input"))
      (node (ref "R90") (pin "1") (pinfunction "1_1") (pintype "passive"))
      (node (ref "R91") (pin "2") (pinfunction "2_2") (pintype "passive"))
    )
    (net (code "33") (name "Net-(IC19A-CLPA)") (class "Default")
      (node (ref "C228") (pin "1") (pinfunction "1_1") (pintype "passive"))
      (node (ref "IC19") (pin "18") (pinfunction "CLPA_18") (pintype "input"))
    )
    (net (code "34") (name "Net-(IC19A-CLPB)") (class "Default")
      (node (ref "C240") (pin "1") (pinfunction "1_1") (pintype "passive"))
      (node (ref "IC19") (pin "7") (pinfunction "CLPB_7") (pintype "input"))
    )
    (net (code "35") (name "Net-(IC19A-FBKA)") (class "Default")
      (node (ref "IC19") (pin "13") (pinfunction "OUTP_13") (pintype "output"))
      (node (ref "IC19") (pin "14") (pinfunction "FBKA_14") (pintype "input"))
    )
    (net (code "36") (name "Net-(IC19A-FBKB)") (class "Default")
      (node (ref "IC19") (pin "11") (pinfunction "FBKB_11") (pintype "input"))
      (node (ref "IC19") (pin "12") (pinfunction "OUTN_12") (pintype "output"))
    )
    (net (code "37") (name "Net-(IC19A-PWDN)") (class "Default")
      (node (ref "IC19") (pin "28") (pinfunction "PWDN_28") (pintype "input"))
      (node (ref "R108") (pin "1") (pinfunction "1_1") (pintype "passive"))
    )
    (net (code "38") (name "Net-(IC19A-VLVL)") (class "Default")
      (node (ref "IC19") (pin "6") (pinfunction "VLVL_6") (pintype "input"))
      (node (ref "R107") (pin "1") (pinfunction "1_1") (pintype "passive"))
    )
    (net (code "39") (name "Net-(IC19A-VSTA)") (class "Default")
      (node (ref "IC19") (pin "17") (pinfunction "VSTA_17") (pintype "input"))
      (node (ref "R92") (pin "2") (pinfunction "2_2") (pintype "passive"))
    )
    (net (code "40") (name "Net-(IC19A-VSTB)") (class "Default")
      (node (ref "IC19") (pin "8") (pinfunction "VSTB_8") (pintype "input"))
      (node (ref "R100") (pin "2") (pinfunction "2_2") (pintype "passive"))
    )
    (net (code "41") (name "Net-(IC19B-VPSA)") (class "Default")
      (node (ref "C229") (pin "2") (pinfunction "2_2") (pintype "passive"))
      (node (ref "C234") (pin "2") (pinfunction "2_2") (pintype "passive"))
      (node (ref "C235") (pin "2") (pinfunction "2_2") (pintype "passive"))
      (node (ref "C237") (pin "2") (pinfunction "2_2") (pintype "passive"))
      (node (ref "C238") (pin "2") (pinfunction "2_2") (pintype "passive"))
      (node (ref "C241") (pin "2") (pinfunction "2_2") (pintype "passive"))
      (node (ref "C242") (pin "2") (pinfunction "2_2") (pintype "passive"))
      (node (ref "FR71") (pin "2") (pinfunction "2_2") (pintype "passive"))
      (node (ref "IC19") (pin "20") (pinfunction "VPSR_20") (pintype "power_in"))
      (node (ref "IC19") (pin "22") (pinfunction "VPSA_22") (pintype "power_in"))
      (node (ref "IC19") (pin "3") (pinfunction "VPSB_3") (pintype "power_in"))
    )
    (net (code "42") (name "Net-(IC20-AIN)") (class "Default")
      (node (ref "C236") (pin "2") (pinfunction "2_2") (pintype "passive"))
      (node (ref "IC20") (pin "1") (pinfunction "AIN_1") (pintype "input"))
      (node (ref "R102") (pin "1") (pinfunction "1_1") (pintype "passive"))
    )
    (net (code "43") (name "Net-(IC20-REF)") (class "Default")
      (node (ref "C243") (pin "2") (pinfunction "2_2") (pintype "passive"))
      (node (ref "C244") (pin "1") (pinfunction "1_1") (pintype "passive"))
      (node (ref "IC20") (pin "3") (pinfunction "REF_3") (pintype "input"))
      (node (ref "R103") (pin "1") (pinfunction "1_1") (pintype "passive"))
      (node (ref "R104") (pin "2") (pinfunction "2_2") (pintype "passive"))
    )
    (net (code "44") (name "Net-(IC21-CLKin0)") (class "Default")
      (node (ref "C250") (pin "1") (pinfunction "1_1") (pintype "passive"))
      (node (ref "IC21") (pin "13") (pinfunction "CLKin0_13") (pintype "input"))
    )
    (net (code "45") (name "Net-(IC21-CLKin0*)") (class "Default")
      (node (ref "C251") (pin "2") (pinfunction "2_2") (pintype "passive"))
      (node (ref "IC21") (pin "14") (pinfunction "CLKin0*_14") (pintype "input"))
    )
    (net (code "46") (name "Net-(IC21-OE)") (class "Default")
      (node (ref "IC21") (pin "31") (pinfunction "OE_31") (pintype "input"))
      (node (ref "R110") (pin "2") (pinfunction "2_2") (pintype "passive"))
    )
    (net (code "47") (name "Net-(IC22-RF1)") (class "Default")
      (node (ref "C253") (pin "1") (pinfunction "1_1") (pintype "passive"))
      (node (ref "IC22") (pin "14") (pinfunction "RF1_14") (pintype "bidirectional"))
    )
    (net (code "48") (name "Net-(IC22-RF2)") (class "Default")
      (node (ref "C254") (pin "1") (pinfunction "1_1") (pintype "passive"))
      (node (ref "IC22") (pin "11") (pinfunction "RF2_11") (pintype "bidirectional"))
    )
    (net (code "49") (name "Net-(IC22-RF3)") (class "Default")
      (node (ref "C255") (pin "1") (pinfunction "1_1") (pintype "passive"))
      (node (ref "IC22") (pin "8") (pinfunction "RF3_8") (pintype "bidirectional"))
    )
    (net (code "50") (name "Net-(IC22-RF4)") (class "Default")
      (node (ref "C256") (pin "1") (pinfunction "1_1") (pintype "passive"))
      (node (ref "IC22") (pin "5") (pinfunction "RF4_5") (pintype "bidirectional"))
    )
    (net (code "51") (name "Net-(IC22-RFC)") (class "Default")
      (node (ref "C252") (pin "2") (pinfunction "2_2") (pintype "passive"))
      (node (ref "IC22") (pin "22") (pinfunction "RFC_22") (pintype "bidirectional"))
    )
    (net (code "52") (name "Net-(J21-X)") (class "Default")
      (node (ref "C252") (pin "1") (pinfunction "1_1") (pintype "passive"))
      (node (ref "ESD25") (pin "1") (pinfunction "1_1") (pintype "passive"))
      (node (ref "J21") (pin "1") (pinfunction "X_1") (pintype "passive"))
    )
    (net (code "53") (name "Net-(J22-X)") (class "Default")
      (node (ref "C256") (pin "2") (pinfunction "2_2") (pintype "passive"))
      (node (ref "ESD21") (pin "1") (pinfunction "1_1") (pintype "passive"))
      (node (ref "J22") (pin "1") (pinfunction "X_1") (pintype "passive"))
    )
    (net (code "54") (name "Net-(J23-X)") (class "Default")
      (node (ref "C255") (pin "2") (pinfunction "2_2") (pintype "passive"))
      (node (ref "ESD22") (pin "1") (pinfunction "1_1") (pintype "passive"))
      (node (ref "J23") (pin "1") (pinfunction "X_1") (pintype "passive"))
    )
    (net (code "55") (name "Net-(J24-X)") (class "Default")
      (node (ref "C254") (pin "2") (pinfunction "2_2") (pintype "passive"))
      (node (ref "ESD23") (pin "1") (pinfunction "1_1") (pintype "passive"))
      (node (ref "J24") (pin "1") (pinfunction "X_1") (pintype "passive"))
    )
    (net (code "56") (name "Net-(J25-X)") (class "Default")
      (node (ref "C253") (pin "2") (pinfunction "2_2") (pintype "passive"))
      (node (ref "ESD24") (pin "1") (pinfunction "1_1") (pintype "passive"))
      (node (ref "J25") (pin "1") (pinfunction "X_1") (pintype "passive"))
    )
    (net (code "57") (name "VCC1P5") (class "Default")
      (node (ref "C230") (pin "2") (pinfunction "2_2") (pintype "passive"))
      (node (ref "C231") (pin "1") (pinfunction "1_1") (pintype "passive"))
      (node (ref "C245") (pin "2") (pinfunction "2_2") (pintype "passive"))
      (node (ref "C246") (pin "1") (pinfunction "1_1") (pintype "passive"))
      (node (ref "FR73") (pin "1") (pinfunction "1_1") (pintype "passive"))
      (node (ref "IC18") (pin "7") (pinfunction "OVDD_7") (pintype "power_in"))
      (node (ref "IC20") (pin "7") (pinfunction "OVDD_7") (pintype "power_in"))
    )
    (net (code "58") (name "VCC1P8") (class "Default")
      (node (ref "R111") (pin "1") (pinfunction "1_1") (pintype "passive"))
      (node (ref "R112") (pin "1") (pinfunction "1_1") (pintype "passive"))
      (node (ref "R113") (pin "1") (pinfunction "1_1") (pintype "passive"))
    )
    (net (code "59") (name "VCC3P3") (class "Default")
      (node (ref "C232") (pin "2") (pinfunction "2_2") (pintype "passive"))
      (node (ref "C233") (pin "1") (pinfunction "1_1") (pintype "passive"))
      (node (ref "C247") (pin "2") (pinfunction "2_2") (pintype "passive"))
      (node (ref "C248") (pin "1") (pinfunction "1_1") (pintype "passive"))
      (node (ref "FR72") (pin "1") (pinfunction "1_1") (pintype "passive"))
      (node (ref "IC18") (pin "4") (pinfunction "VDD_4") (pintype "power_in"))
      (node (ref "IC20") (pin "4") (pinfunction "VDD_4") (pintype "power_in"))
    )
    (net (code "60") (name "VCC3P3_CLK") (class "Default")
      (node (ref "FR74") (pin "1") (pinfunction "1_1") (pintype "passive"))
      (node (ref "R103") (pin "2") (pinfunction "2_2") (pintype "passive"))
      (node (ref "R90") (pin "2") (pinfunction "2_2") (pintype "passive"))
    )
    (net (code "61") (name "VCC3P3_RF") (class "Default")
      (node (ref "C257") (pin "2") (pinfunction "2_2") (pintype "passive"))
      (node (ref "C258") (pin "2") (pinfunction "2_2") (pintype "passive"))
      (node (ref "C259") (pin "2") (pinfunction "2_2") (pintype "passive"))
      (node (ref "C260") (pin "2") (pinfunction "2_2") (pintype "passive"))
      (node (ref "FR72") (pin "2") (pinfunction "2_2") (pintype "passive"))
      (node (ref "IC22") (pin "16") (pinfunction "VDD_16") (pintype "power_in"))
    )
    (net (code "62") (name "VCC5P0") (class "Default")
      (node (ref "FR71") (pin "1") (pinfunction "1_1") (pintype "passive"))
    )
    (net (code "63") (name "unconnected-(IC19A-TEMP-Pad19)") (class "Default")
      (node (ref "IC19") (pin "19") (pinfunction "TEMP_19") (pintype "output+no_connect"))
    )
    (net (code "64") (name "unconnected-(IC19B-NC-Pad9)") (class "Default")
      (node (ref "IC19") (pin "9") (pinfunction "NC_9") (pintype "passive+no_connect"))
    )
    (net (code "65") (name "unconnected-(IC19B-NC-Pad16)") (class "Default")
      (node (ref "IC19") (pin "16") (pinfunction "NC_16") (pintype "passive+no_connect"))
    )
    (net (code "66") (name "unconnected-(IC21-CLKin1*-Pad27)") (class "Default")
      (node (ref "IC21") (pin "27") (pinfunction "CLKin1*_27") (pintype "input+no_connect"))
    )
    (net (code "67") (name "unconnected-(IC21-CLKin1-Pad28)") (class "Default")
      (node (ref "IC21") (pin "28") (pinfunction "CLKin1_28") (pintype "input+no_connect"))
    )
    (net (code "68") (name "unconnected-(IC21-CLKout6-Pad18)") (class "Default")
      (node (ref "IC21") (pin "18") (pinfunction "CLKout6_18") (pintype "output+no_connect"))
    )
    (net (code "69") (name "unconnected-(IC21-CLKout7-Pad20)") (class "Default")
      (node (ref "IC21") (pin "20") (pinfunction "CLKout7_20") (pintype "output+no_connect"))
    )
    (net (code "70") (name "unconnected-(IC21-CLKout8-Pad22)") (class "Default")
      (node (ref "IC21") (pin "22") (pinfunction "CLKout8_22") (pintype "output+no_connect"))
    )
    (net (code "71") (name "unconnected-(IC21-CLKout9-Pad24)") (class "Default")
      (node (ref "IC21") (pin "24") (pinfunction "CLKout9_24") (pintype "output+no_connect"))
    )
    (net (code "72") (name "unconnected-(IC21-OSCin-Pad11)") (class "Default")
      (node (ref "IC21") (pin "11") (pinfunction "OSCin_11") (pintype "input+no_connect"))
    )
    (net (code "73") (name "unconnected-(IC21-OSCout-Pad12)") (class "Default")
      (node (ref "IC21") (pin "12") (pinfunction "OSCout_12") (pintype "output+no_connect"))
    )
  )
)
